# SparkFun_Qwiic_Encryption_ATECC508A.net
KiCad netlist of a schematic drawn in EAGLE
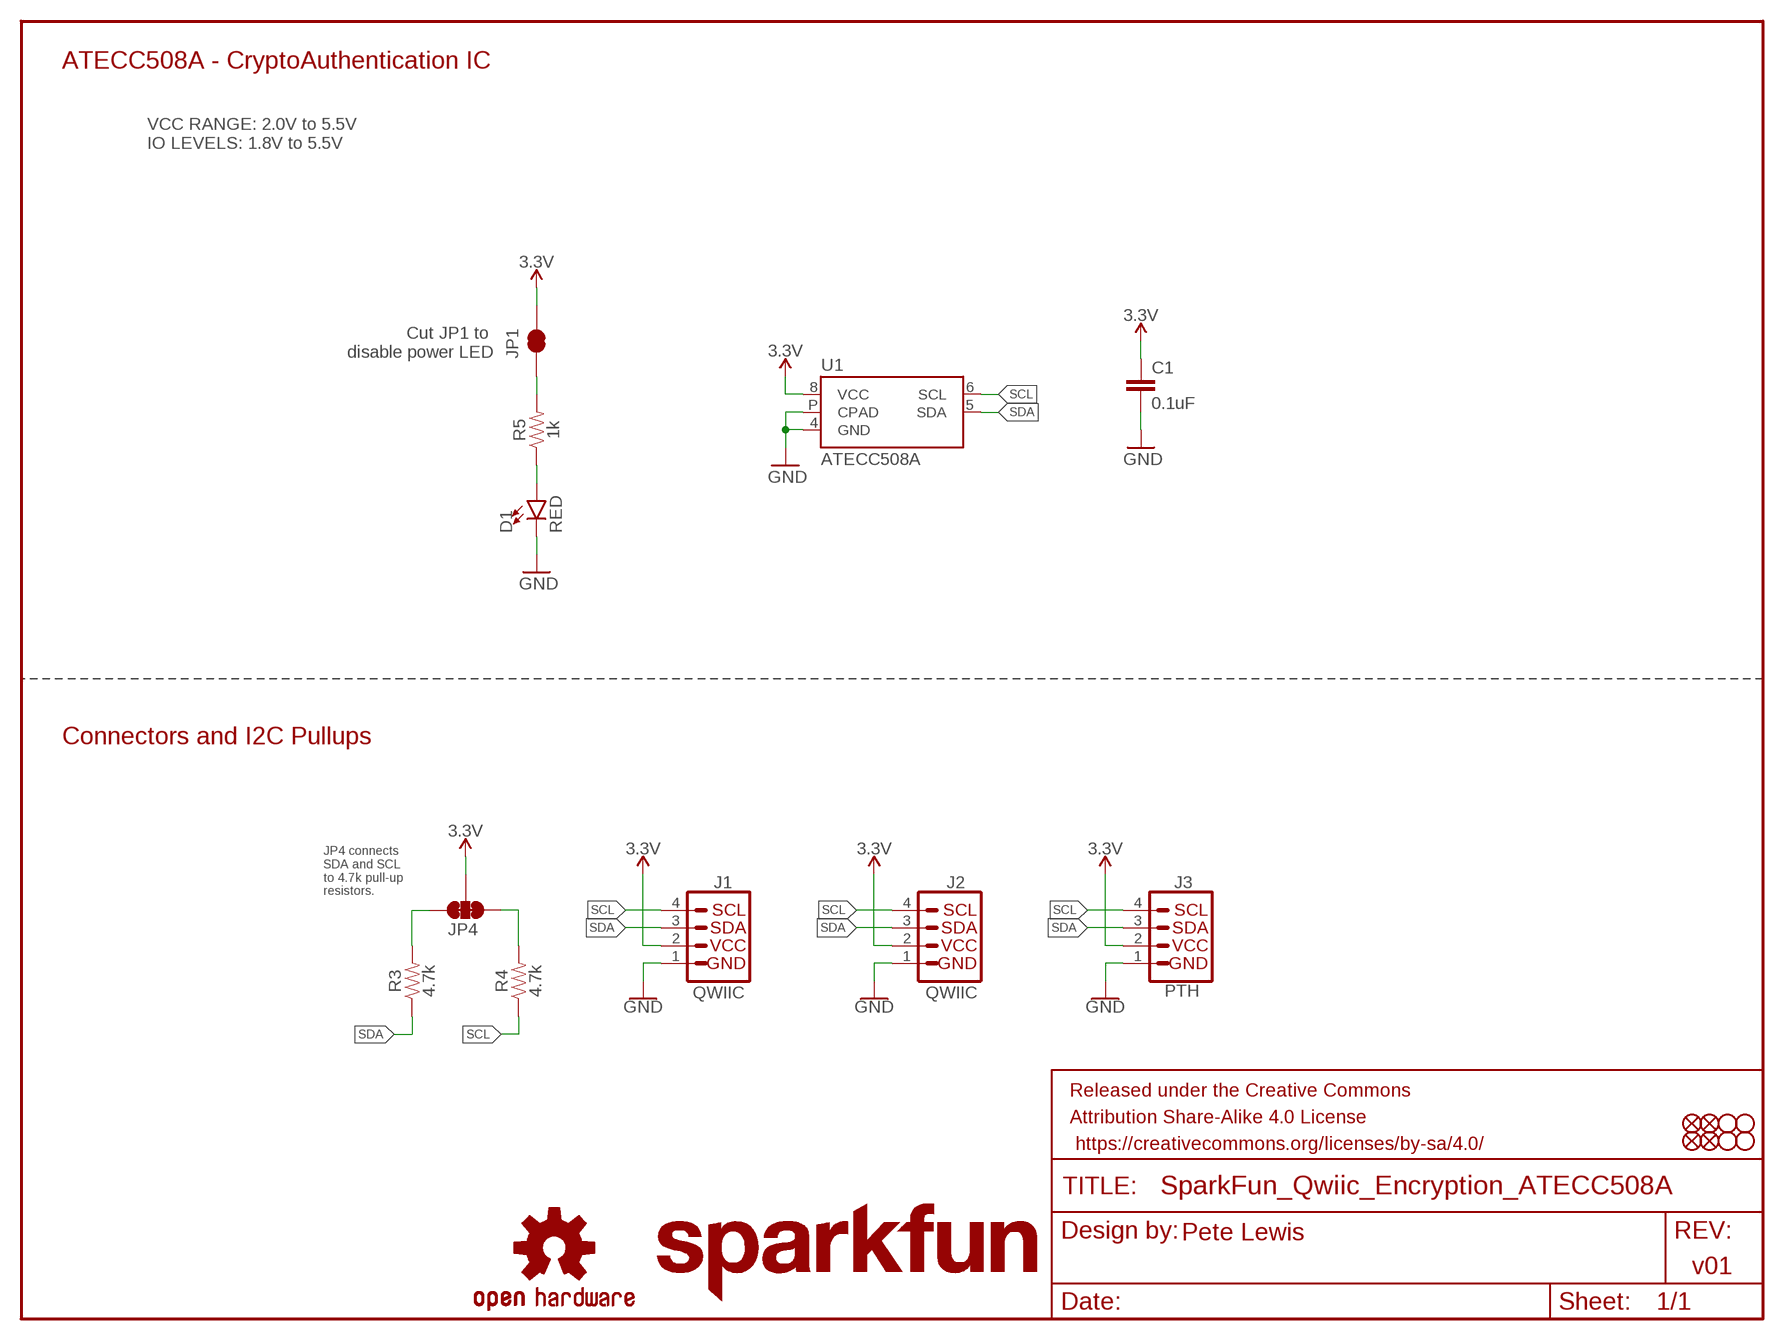
[diagram p0: schematic, sheet 1]

(export (version "E")
  (design (tool "Eeschema 10.0.6"))
  (components
    (comp (ref "C1")
      (value "0.1uF")
      (footprint "eagle-import:0603")
      (libsource (lib "eagle-import") (part "0.1UF-0603-25V-(+80/-20%)"))
    )
    (comp (ref "D1")
      (value "RED")
      (footprint "eagle-import:LED-0603")
      (libsource (lib "eagle-import") (part "LED-RED0603"))
    )
    (comp (ref "FD1")
      (value "FIDUCIAL1X2")
      (footprint "eagle-import:FIDUCIAL-1X2")
      (libsource (lib "eagle-import") (part "FIDUCIAL1X2"))
    )
    (comp (ref "FD2")
      (value "FIDUCIAL1X2")
      (footprint "eagle-import:FIDUCIAL-1X2")
      (libsource (lib "eagle-import") (part "FIDUCIAL1X2"))
    )
    (comp (ref "FD3")
      (value "FIDUCIAL1X2")
      (footprint "eagle-import:FIDUCIAL-1X2")
      (libsource (lib "eagle-import") (part "FIDUCIAL1X2"))
    )
    (comp (ref "FD4")
      (value "FIDUCIAL1X2")
      (footprint "eagle-import:FIDUCIAL-1X2")
      (libsource (lib "eagle-import") (part "FIDUCIAL1X2"))
    )
    (comp (ref "FRAME1")
      (value "FRAME-LETTER")
      (footprint "eagle-import:CREATIVE_COMMONS")
      (libsource (lib "eagle-import") (part "FRAME-LETTER"))
    )
    (comp (ref "H1")
      (value "STAND-OFF")
      (footprint "eagle-import:STAND-OFF")
      (libsource (lib "eagle-import") (part "STAND-OFF"))
    )
    (comp (ref "H2")
      (value "STAND-OFF")
      (footprint "eagle-import:STAND-OFF")
      (libsource (lib "eagle-import") (part "STAND-OFF"))
    )
    (comp (ref "H3")
      (value "STAND-OFF")
      (footprint "eagle-import:STAND-OFF")
      (libsource (lib "eagle-import") (part "STAND-OFF"))
    )
    (comp (ref "H4")
      (value "STAND-OFF")
      (footprint "eagle-import:STAND-OFF")
      (libsource (lib "eagle-import") (part "STAND-OFF"))
    )
    (comp (ref "J1")
      (value "QWIIC")
      (footprint "eagle-import:JST04_1MM_RA")
      (libsource (lib "eagle-import") (part "I2C_STANDARDQWIIC"))
    )
    (comp (ref "J2")
      (value "QWIIC")
      (footprint "eagle-import:JST04_1MM_RA")
      (libsource (lib "eagle-import") (part "I2C_STANDARDQWIIC"))
    )
    (comp (ref "J3")
      (value "PTH")
      (footprint "eagle-import:1X04_NO_SILK")
      (libsource (lib "eagle-import") (part "I2C_STANDARD_NO_SILK"))
    )
    (comp (ref "JP1")
      (value "JUMPER-SMT_2_NC_TRACE_NO-SILK")
      (footprint "eagle-import:SMT-JUMPER_2_NC_TRACE_NO-SILK")
      (libsource (lib "eagle-import") (part "JUMPER-SMT_2_NC_TRACE_NO-SILK"))
    )
    (comp (ref "JP4")
      (value "JUMPER-SMT_3_2-NC_TRACE_NO-SILK")
      (footprint "eagle-import:SMT-JUMPER_3_2-NC_TRACE_NO-SILK")
      (libsource (lib "eagle-import") (part "JUMPER-SMT_3_2-NC_TRACE_NO-SILK"))
    )
    (comp (ref "LOGO1")
      (value "SFE_LOGO_NAME.1_INCH")
      (footprint "eagle-import:SFE_LOGO_NAME_.1")
      (libsource (lib "eagle-import") (part "SFE_LOGO_NAME.1_INCH"))
    )
    (comp (ref "LOGO4")
      (value "OSHW-LOGOS")
      (footprint "eagle-import:OSHW-LOGO-S")
      (libsource (lib "eagle-import") (part "OSHW-LOGOS"))
    )
    (comp (ref "R3")
      (value "4.7k")
      (footprint "eagle-import:0603")
      (libsource (lib "eagle-import") (part "4.7KOHM-0603-1/10W-1%"))
    )
    (comp (ref "R4")
      (value "4.7k")
      (footprint "eagle-import:0603")
      (libsource (lib "eagle-import") (part "4.7KOHM-0603-1/10W-1%"))
    )
    (comp (ref "R5")
      (value "1k")
      (footprint "eagle-import:0603")
      (libsource (lib "eagle-import") (part "1KOHM-0603-1/10W-1%"))
    )
    (comp (ref "U1")
      (value "ATECC508A")
      (footprint "eagle-import:UDFN_2X3MM")
      (libsource (lib "eagle-import") (part "ATECC508AUDFN_2X3MM"))
    )
  )
  (nets
    (net (code "1") (name "3.3V") (class "Default")
      (node (ref "C1") (pin "1") (pinfunction "1_1") (pintype "passive"))
      (node (ref "J1") (pin "2") (pinfunction "2_2") (pintype "power_in"))
      (node (ref "J2") (pin "2") (pinfunction "2_2") (pintype "power_in"))
      (node (ref "J3") (pin "2") (pinfunction "2_2") (pintype "power_in"))
      (node (ref "JP1") (pin "2") (pinfunction "2_2") (pintype "passive"))
      (node (ref "JP4") (pin "2") (pinfunction "2_2") (pintype "passive"))
      (node (ref "U1") (pin "8") (pinfunction "VCC_8") (pintype "power_in"))
    )
    (net (code "2") (name "GND") (class "Default")
      (node (ref "C1") (pin "2") (pinfunction "2_2") (pintype "passive"))
      (node (ref "D1") (pin "C") (pinfunction "C_C") (pintype "passive"))
      (node (ref "J1") (pin "1") (pinfunction "1_1") (pintype "power_in"))
      (node (ref "J2") (pin "1") (pinfunction "1_1") (pintype "power_in"))
      (node (ref "J3") (pin "1") (pinfunction "1_1") (pintype "power_in"))
      (node (ref "U1") (pin "4") (pinfunction "GND_4") (pintype "power_in"))
      (node (ref "U1") (pin "P") (pinfunction "CPAD_P") (pintype "power_in"))
    )
    (net (code "3") (name "Net-(D1-PadA)") (class "Default")
      (node (ref "D1") (pin "A") (pinfunction "A_A") (pintype "passive"))
      (node (ref "R5") (pin "1") (pinfunction "1_1") (pintype "passive"))
    )
    (net (code "4") (name "Net-(JP1-Pad1)") (class "Default")
      (node (ref "JP1") (pin "1") (pinfunction "1_1") (pintype "passive"))
      (node (ref "R5") (pin "2") (pinfunction "2_2") (pintype "passive"))
    )
    (net (code "5") (name "Net-(JP4-Pad1)") (class "Default")
      (node (ref "JP4") (pin "1") (pinfunction "1_1") (pintype "passive"))
      (node (ref "R4") (pin "2") (pinfunction "2_2") (pintype "passive"))
    )
    (net (code "6") (name "Net-(JP4-Pad3)") (class "Default")
      (node (ref "JP4") (pin "3") (pinfunction "3_3") (pintype "passive"))
      (node (ref "R3") (pin "2") (pinfunction "2_2") (pintype "passive"))
    )
    (net (code "7") (name "SCL") (class "Default")
      (node (ref "J1") (pin "4") (pinfunction "4_4") (pintype "passive"))
      (node (ref "J2") (pin "4") (pinfunction "4_4") (pintype "passive"))
      (node (ref "J3") (pin "4") (pinfunction "4_4") (pintype "passive"))
      (node (ref "R4") (pin "1") (pinfunction "1_1") (pintype "passive"))
      (node (ref "U1") (pin "6") (pinfunction "SCL_6") (pintype "bidirectional"))
    )
    (net (code "8") (name "SDA") (class "Default")
      (node (ref "J1") (pin "3") (pinfunction "3_3") (pintype "passive"))
      (node (ref "J2") (pin "3") (pinfunction "3_3") (pintype "passive"))
      (node (ref "J3") (pin "3") (pinfunction "3_3") (pintype "passive"))
      (node (ref "R3") (pin "1") (pinfunction "1_1") (pintype "passive"))
      (node (ref "U1") (pin "5") (pinfunction "SDA_5") (pintype "bidirectional"))
    )
  )
)
